# io-headers.net
KiCad netlist of a schematic drawn in Altium Designer
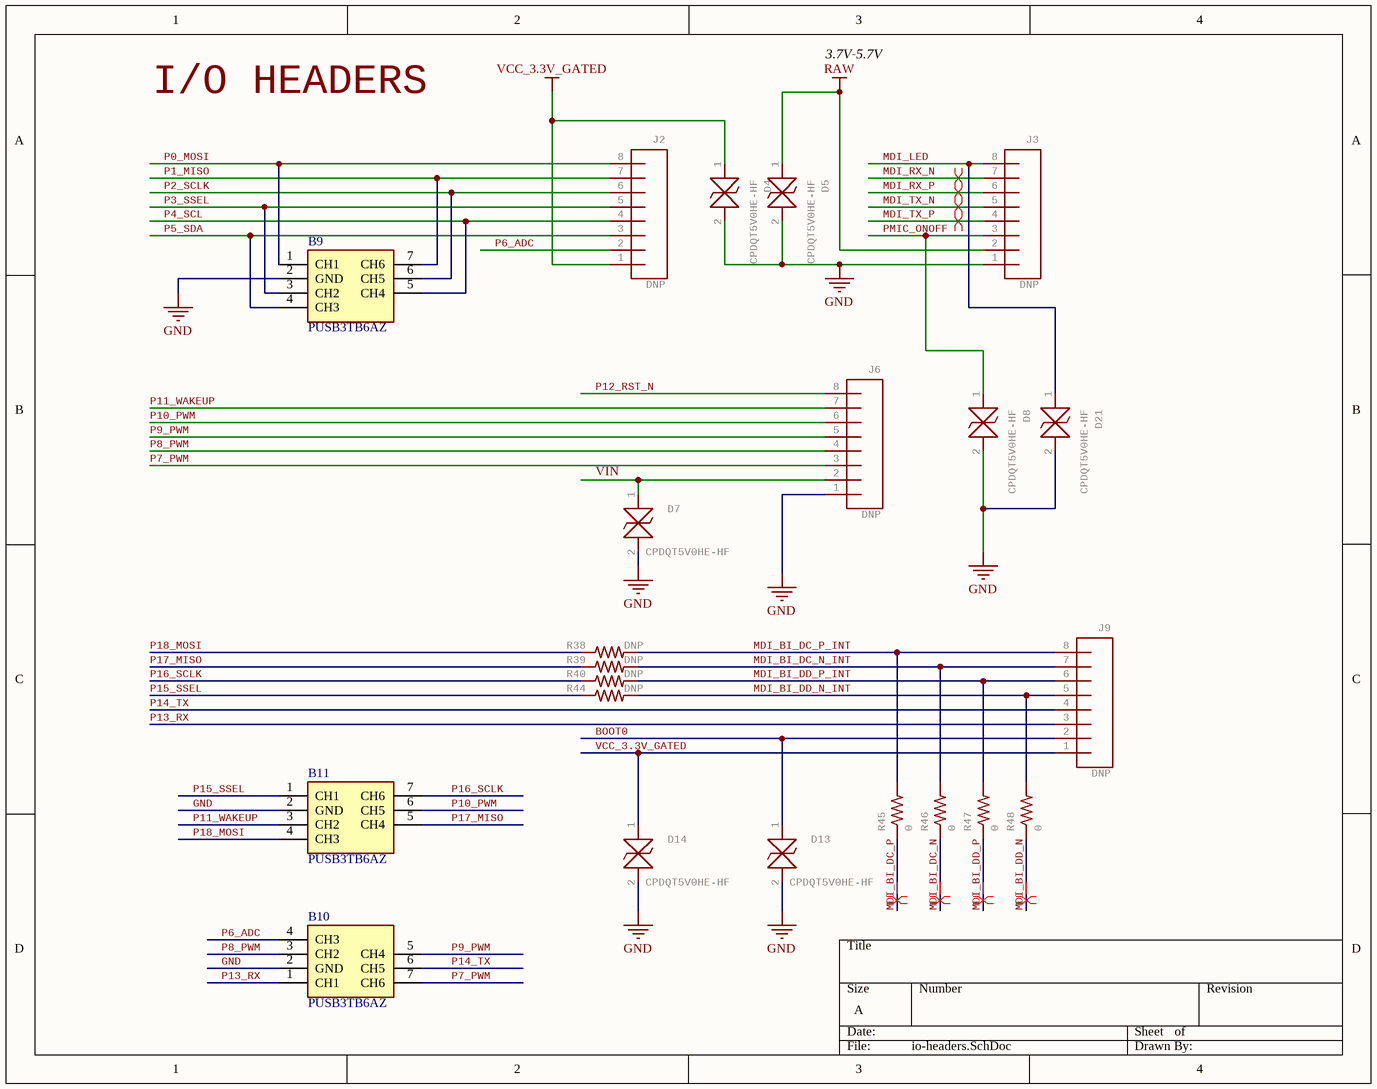
[diagram p0: io-headers.SchDoc]

(export (version "E")
  (design (tool "Eeschema 10.0.6"))
  (components
    (comp (ref "B9")
      (value "PUSB3TB6AZ")
      (footprint "PUSB3TB6AZ")
      (description "NEXPERIA - PUSB3TB6AZ - DIODE, ESD PROTECTION, 5.5V, 0.27PF")
      (fields (field (name "MOUSER PART NUMBER") "771-PUSB3TB6AZ"))
      (libsource (lib "PUSB3TB6AZ") (part "PUSB3TB6AZ"))
    )
    (comp (ref "B10")
      (value "PUSB3TB6AZ")
      (footprint "PUSB3TB6AZ")
      (description "NEXPERIA - PUSB3TB6AZ - DIODE, ESD PROTECTION, 5.5V, 0.27PF")
      (fields (field (name "MOUSER PART NUMBER") "771-PUSB3TB6AZ"))
      (libsource (lib "") (part "PUSB3TB6AZ_1"))
    )
    (comp (ref "B11")
      (value "PUSB3TB6AZ")
      (footprint "PUSB3TB6AZ")
      (description "NEXPERIA - PUSB3TB6AZ - DIODE, ESD PROTECTION, 5.5V, 0.27PF")
      (fields (field (name "MOUSER PART NUMBER") "771-PUSB3TB6AZ"))
      (libsource (lib "PUSB3TB6AZ") (part "PUSB3TB6AZ"))
    )
    (comp (ref "D4")
      (value "CPDQT5V0HE-HF")
      (footprint "CPDQT5V0HEHF")
      (description "ESD Suppressors / TVS Diodes DIODE ESD 5VWM 65W 0402/SOD-923F   Source:  Datasheet")
      (fields (field (name "MOUSER_PART_NUMBER") "MOUSER_PART_NUMBER"))
      (libsource (lib "rt10") (part "CPDQT5V0HE-HF"))
    )
    (comp (ref "D5")
      (value "CPDQT5V0HE-HF")
      (footprint "CPDQT5V0HEHF")
      (description "ESD Suppressors / TVS Diodes DIODE ESD 5VWM 65W 0402/SOD-923F   Source:  Datasheet")
      (fields (field (name "MOUSER_PART_NUMBER") "MOUSER_PART_NUMBER"))
      (libsource (lib "rt10") (part "CPDQT5V0HE-HF"))
    )
    (comp (ref "D7")
      (value "CPDQT5V0HE-HF")
      (footprint "CPDQT5V0HEHF")
      (description "ESD Suppressors / TVS Diodes DIODE ESD 5VWM 65W 0402/SOD-923F   Source:  Datasheet")
      (fields (field (name "MOUSER_PART_NUMBER") "MOUSER_PART_NUMBER"))
      (libsource (lib "rt10") (part "CPDQT5V0HE-HF"))
    )
    (comp (ref "D8")
      (value "CPDQT5V0HE-HF")
      (footprint "CPDQT5V0HEHF")
      (description "ESD Suppressors / TVS Diodes DIODE ESD 5VWM 65W 0402/SOD-923F   Source:  Datasheet")
      (fields (field (name "MOUSER_PART_NUMBER") "MOUSER_PART_NUMBER"))
      (libsource (lib "rt10") (part "CPDQT5V0HE-HF"))
    )
    (comp (ref "D13")
      (value "CPDQT5V0HE-HF")
      (footprint "CPDQT5V0HEHF")
      (description "ESD Suppressors / TVS Diodes DIODE ESD 5VWM 65W 0402/SOD-923F   Source:  Datasheet")
      (fields (field (name "MOUSER_PART_NUMBER") "MOUSER_PART_NUMBER"))
      (libsource (lib "rt10") (part "CPDQT5V0HE-HF"))
    )
    (comp (ref "D14")
      (value "CPDQT5V0HE-HF")
      (footprint "CPDQT5V0HEHF")
      (description "ESD Suppressors / TVS Diodes DIODE ESD 5VWM 65W 0402/SOD-923F   Source:  Datasheet")
      (fields (field (name "MOUSER_PART_NUMBER") "MOUSER_PART_NUMBER"))
      (libsource (lib "rt10") (part "CPDQT5V0HE-HF"))
    )
    (comp (ref "D21")
      (value "CPDQT5V0HE-HF")
      (footprint "CPDQT5V0HEHF")
      (description "ESD Suppressors / TVS Diodes DIODE ESD 5VWM 65W 0402/SOD-923F   Source:  Datasheet")
      (fields (field (name "MOUSER_PART_NUMBER") "MOUSER_PART_NUMBER"))
      (libsource (lib "rt10") (part "CPDQT5V0HE-HF"))
    )
    (comp (ref "J2") (value "DNP") (footprint "1X08") (libsource (lib "rt10") (part "CONN_08{dblquote}")))
    (comp (ref "J3") (value "DNP") (footprint "1X08") (libsource (lib "rt10") (part "CONN_08{dblquote}")))
    (comp (ref "J6") (value "DNP") (footprint "1X08") (libsource (lib "rt10") (part "CONN_08{dblquote}")))
    (comp (ref "J9") (value "DNP") (footprint "1X08") (libsource (lib "rt10") (part "CONN_08{dblquote}")))
    (comp (ref "R38")
      (value "DNP")
      (footprint "0402-RES")
      (description "ResistorBasic schematic elements and footprints for 0603, 1206, and PTH resistors.")
      (libsource (lib "openmv-ae3") (part "RESISTOR0402-RES"))
    )
    (comp (ref "R39")
      (value "DNP")
      (footprint "0402-RES")
      (description "ResistorBasic schematic elements and footprints for 0603, 1206, and PTH resistors.")
      (libsource (lib "openmv-ae3") (part "RESISTOR0402-RES"))
    )
    (comp (ref "R40")
      (value "DNP")
      (footprint "0402-RES")
      (description "ResistorBasic schematic elements and footprints for 0603, 1206, and PTH resistors.")
      (libsource (lib "openmv-ae3") (part "RESISTOR0402-RES"))
    )
    (comp (ref "R44")
      (value "DNP")
      (footprint "0402-RES")
      (description "ResistorBasic schematic elements and footprints for 0603, 1206, and PTH resistors.")
      (libsource (lib "openmv-ae3") (part "RESISTOR0402-RES"))
    )
    (comp (ref "R45")
      (value "0")
      (footprint "0402-RES")
      (description "ResistorBasic schematic elements and footprints for 0603, 1206, and PTH resistors.")
      (fields (field (name "MPN") "RC0402JR-070R"))
      (libsource (lib "openmv-ae3") (part "RESISTOR0402-RES"))
    )
    (comp (ref "R46")
      (value "0")
      (footprint "0402-RES")
      (description "ResistorBasic schematic elements and footprints for 0603, 1206, and PTH resistors.")
      (fields (field (name "MPN") "RC0402JR-070R"))
      (libsource (lib "openmv-ae3") (part "RESISTOR0402-RES"))
    )
    (comp (ref "R47")
      (value "0")
      (footprint "0402-RES")
      (description "ResistorBasic schematic elements and footprints for 0603, 1206, and PTH resistors.")
      (fields (field (name "MPN") "RC0402JR-070R"))
      (libsource (lib "openmv-ae3") (part "RESISTOR0402-RES"))
    )
    (comp (ref "R48")
      (value "0")
      (footprint "0402-RES")
      (description "ResistorBasic schematic elements and footprints for 0603, 1206, and PTH resistors.")
      (fields (field (name "MPN") "RC0402JR-070R"))
      (libsource (lib "openmv-ae3") (part "RESISTOR0402-RES"))
    )
  )
  (nets
    (net (code "1") (name "/BOOT0") (class "Default")
      (node (ref "D13") (pin "1") (pinfunction "1_1") (pintype "bidirectional"))
      (node (ref "J9") (pin "2") (pinfunction "2_2") (pintype "passive"))
    )
    (net (code "2") (name "/MDI_BI_DC_N") (class "Default")
      (node (ref "R46") (pin "1") (pinfunction "1_1") (pintype "passive"))
    )
    (net (code "3") (name "/MDI_BI_DC_N_INT") (class "Default")
      (node (ref "J9") (pin "7") (pinfunction "7_7") (pintype "passive"))
      (node (ref "R39") (pin "2") (pinfunction "2_2") (pintype "passive"))
      (node (ref "R46") (pin "2") (pinfunction "2_2") (pintype "passive"))
    )
    (net (code "4") (name "/MDI_BI_DC_P") (class "Default")
      (node (ref "R45") (pin "1") (pinfunction "1_1") (pintype "passive"))
    )
    (net (code "5") (name "/MDI_BI_DC_P_INT") (class "Default")
      (node (ref "J9") (pin "8") (pinfunction "8_8") (pintype "passive"))
      (node (ref "R38") (pin "2") (pinfunction "2_2") (pintype "passive"))
      (node (ref "R45") (pin "2") (pinfunction "2_2") (pintype "passive"))
    )
    (net (code "6") (name "/MDI_BI_DD_N") (class "Default")
      (node (ref "R48") (pin "1") (pinfunction "1_1") (pintype "passive"))
    )
    (net (code "7") (name "/MDI_BI_DD_N_INT") (class "Default")
      (node (ref "J9") (pin "5") (pinfunction "5_5") (pintype "passive"))
      (node (ref "R44") (pin "2") (pinfunction "2_2") (pintype "passive"))
      (node (ref "R48") (pin "2") (pinfunction "2_2") (pintype "passive"))
    )
    (net (code "8") (name "/MDI_BI_DD_P") (class "Default")
      (node (ref "R47") (pin "1") (pinfunction "1_1") (pintype "passive"))
    )
    (net (code "9") (name "/MDI_BI_DD_P_INT") (class "Default")
      (node (ref "J9") (pin "6") (pinfunction "6_6") (pintype "passive"))
      (node (ref "R40") (pin "2") (pinfunction "2_2") (pintype "passive"))
      (node (ref "R47") (pin "2") (pinfunction "2_2") (pintype "passive"))
    )
    (net (code "10") (name "/MDI_LED") (class "Default")
      (node (ref "D21") (pin "1") (pinfunction "1_1") (pintype "bidirectional"))
      (node (ref "J3") (pin "8") (pinfunction "8_8") (pintype "passive"))
    )
    (net (code "11") (name "/MDI_RX_N") (class "Default")
      (node (ref "J3") (pin "7") (pinfunction "7_7") (pintype "passive"))
    )
    (net (code "12") (name "/MDI_RX_P") (class "Default")
      (node (ref "J3") (pin "6") (pinfunction "6_6") (pintype "passive"))
    )
    (net (code "13") (name "/MDI_TX_N") (class "Default")
      (node (ref "J3") (pin "5") (pinfunction "5_5") (pintype "passive"))
    )
    (net (code "14") (name "/MDI_TX_P") (class "Default")
      (node (ref "J3") (pin "4") (pinfunction "4_4") (pintype "passive"))
    )
    (net (code "15") (name "/P0_MOSI") (class "Default")
      (node (ref "B9") (pin "1") (pinfunction "CH1_1") (pintype "passive"))
      (node (ref "J2") (pin "8") (pinfunction "8_8") (pintype "passive"))
    )
    (net (code "16") (name "/P1_MISO") (class "Default")
      (node (ref "B9") (pin "7") (pinfunction "CH6_7") (pintype "passive"))
      (node (ref "J2") (pin "7") (pinfunction "7_7") (pintype "passive"))
    )
    (net (code "17") (name "/P2_SCLK") (class "Default")
      (node (ref "B9") (pin "6") (pinfunction "CH5_6") (pintype "passive"))
      (node (ref "J2") (pin "6") (pinfunction "6_6") (pintype "passive"))
    )
    (net (code "18") (name "/P3_SSEL") (class "Default")
      (node (ref "B9") (pin "3") (pinfunction "CH2_3") (pintype "passive"))
      (node (ref "J2") (pin "5") (pinfunction "5_5") (pintype "passive"))
    )
    (net (code "19") (name "/P4_SCL") (class "Default")
      (node (ref "B9") (pin "5") (pinfunction "CH4_5") (pintype "passive"))
      (node (ref "J2") (pin "4") (pinfunction "4_4") (pintype "passive"))
    )
    (net (code "20") (name "/P5_SDA") (class "Default")
      (node (ref "B9") (pin "4") (pinfunction "CH3_4") (pintype "passive"))
      (node (ref "J2") (pin "3") (pinfunction "3_3") (pintype "passive"))
    )
    (net (code "21") (name "/P6_ADC") (class "Default")
      (node (ref "B10") (pin "4") (pinfunction "CH3_4") (pintype "passive"))
      (node (ref "J2") (pin "2") (pinfunction "2_2") (pintype "passive"))
    )
    (net (code "22") (name "/P7_PWM") (class "Default")
      (node (ref "B10") (pin "7") (pinfunction "CH6_7") (pintype "passive"))
      (node (ref "J6") (pin "3") (pinfunction "3_3") (pintype "passive"))
    )
    (net (code "23") (name "/P8_PWM") (class "Default")
      (node (ref "B10") (pin "3") (pinfunction "CH2_3") (pintype "passive"))
      (node (ref "J6") (pin "4") (pinfunction "4_4") (pintype "passive"))
    )
    (net (code "24") (name "/P9_PWM") (class "Default")
      (node (ref "B10") (pin "5") (pinfunction "CH4_5") (pintype "passive"))
      (node (ref "J6") (pin "5") (pinfunction "5_5") (pintype "passive"))
    )
    (net (code "25") (name "/P10_PWM") (class "Default")
      (node (ref "B11") (pin "6") (pinfunction "CH5_6") (pintype "passive"))
      (node (ref "J6") (pin "6") (pinfunction "6_6") (pintype "passive"))
    )
    (net (code "26") (name "/P11_WAKEUP") (class "Default")
      (node (ref "B11") (pin "3") (pinfunction "CH2_3") (pintype "passive"))
      (node (ref "J6") (pin "7") (pinfunction "7_7") (pintype "passive"))
    )
    (net (code "27") (name "/P12_RST_N") (class "Default")
      (node (ref "J6") (pin "8") (pinfunction "8_8") (pintype "passive"))
    )
    (net (code "28") (name "/P13_RX") (class "Default")
      (node (ref "B10") (pin "1") (pinfunction "CH1_1") (pintype "passive"))
      (node (ref "J9") (pin "3") (pinfunction "3_3") (pintype "passive"))
    )
    (net (code "29") (name "/P14_TX") (class "Default")
      (node (ref "B10") (pin "6") (pinfunction "CH5_6") (pintype "passive"))
      (node (ref "J9") (pin "4") (pinfunction "4_4") (pintype "passive"))
    )
    (net (code "30") (name "/P15_SSEL") (class "Default")
      (node (ref "B11") (pin "1") (pinfunction "CH1_1") (pintype "passive"))
      (node (ref "R44") (pin "1") (pinfunction "1_1") (pintype "passive"))
    )
    (net (code "31") (name "/P16_SCLK") (class "Default")
      (node (ref "B11") (pin "7") (pinfunction "CH6_7") (pintype "passive"))
      (node (ref "R40") (pin "1") (pinfunction "1_1") (pintype "passive"))
    )
    (net (code "32") (name "/P17_MISO") (class "Default")
      (node (ref "B11") (pin "5") (pinfunction "CH4_5") (pintype "passive"))
      (node (ref "R39") (pin "1") (pinfunction "1_1") (pintype "passive"))
    )
    (net (code "33") (name "/P18_MOSI") (class "Default")
      (node (ref "B11") (pin "4") (pinfunction "CH3_4") (pintype "passive"))
      (node (ref "R38") (pin "1") (pinfunction "1_1") (pintype "passive"))
    )
    (net (code "34") (name "/PMIC_ONOFF") (class "Default")
      (node (ref "D8") (pin "1") (pinfunction "1_1") (pintype "bidirectional"))
      (node (ref "J3") (pin "3") (pinfunction "3_3") (pintype "passive"))
    )
    (net (code "35") (name "/VIN") (class "Default")
      (node (ref "D7") (pin "1") (pinfunction "1_1") (pintype "bidirectional"))
      (node (ref "J6") (pin "2") (pinfunction "2_2") (pintype "passive"))
    )
    (net (code "36") (name "GND") (class "Default")
      (node (ref "B10") (pin "2") (pinfunction "GND_2") (pintype "passive"))
      (node (ref "B11") (pin "2") (pinfunction "GND_2") (pintype "passive"))
      (node (ref "B9") (pin "2") (pinfunction "GND_2") (pintype "passive"))
      (node (ref "D13") (pin "2") (pinfunction "2_2") (pintype "bidirectional"))
      (node (ref "D14") (pin "2") (pinfunction "2_2") (pintype "bidirectional"))
      (node (ref "D21") (pin "2") (pinfunction "2_2") (pintype "bidirectional"))
      (node (ref "D4") (pin "2") (pinfunction "2_2") (pintype "bidirectional"))
      (node (ref "D5") (pin "2") (pinfunction "2_2") (pintype "bidirectional"))
      (node (ref "D7") (pin "2") (pinfunction "2_2") (pintype "bidirectional"))
      (node (ref "D8") (pin "2") (pinfunction "2_2") (pintype "bidirectional"))
      (node (ref "J3") (pin "1") (pinfunction "1_1") (pintype "passive"))
      (node (ref "J6") (pin "1") (pinfunction "1_1") (pintype "passive"))
    )
    (net (code "37") (name "RAW") (class "Default")
      (node (ref "D5") (pin "1") (pinfunction "1_1") (pintype "bidirectional"))
      (node (ref "J3") (pin "2") (pinfunction "2_2") (pintype "passive"))
    )
    (net (code "38") (name "VCC_3.3V_GATED") (class "Default")
      (node (ref "D14") (pin "1") (pinfunction "1_1") (pintype "bidirectional"))
      (node (ref "D4") (pin "1") (pinfunction "1_1") (pintype "bidirectional"))
      (node (ref "J2") (pin "1") (pinfunction "1_1") (pintype "passive"))
      (node (ref "J9") (pin "1") (pinfunction "1_1") (pintype "passive"))
    )
  )
)
